# PT08tqfp.net
KiCad netlist of a schematic drawn in EAGLE
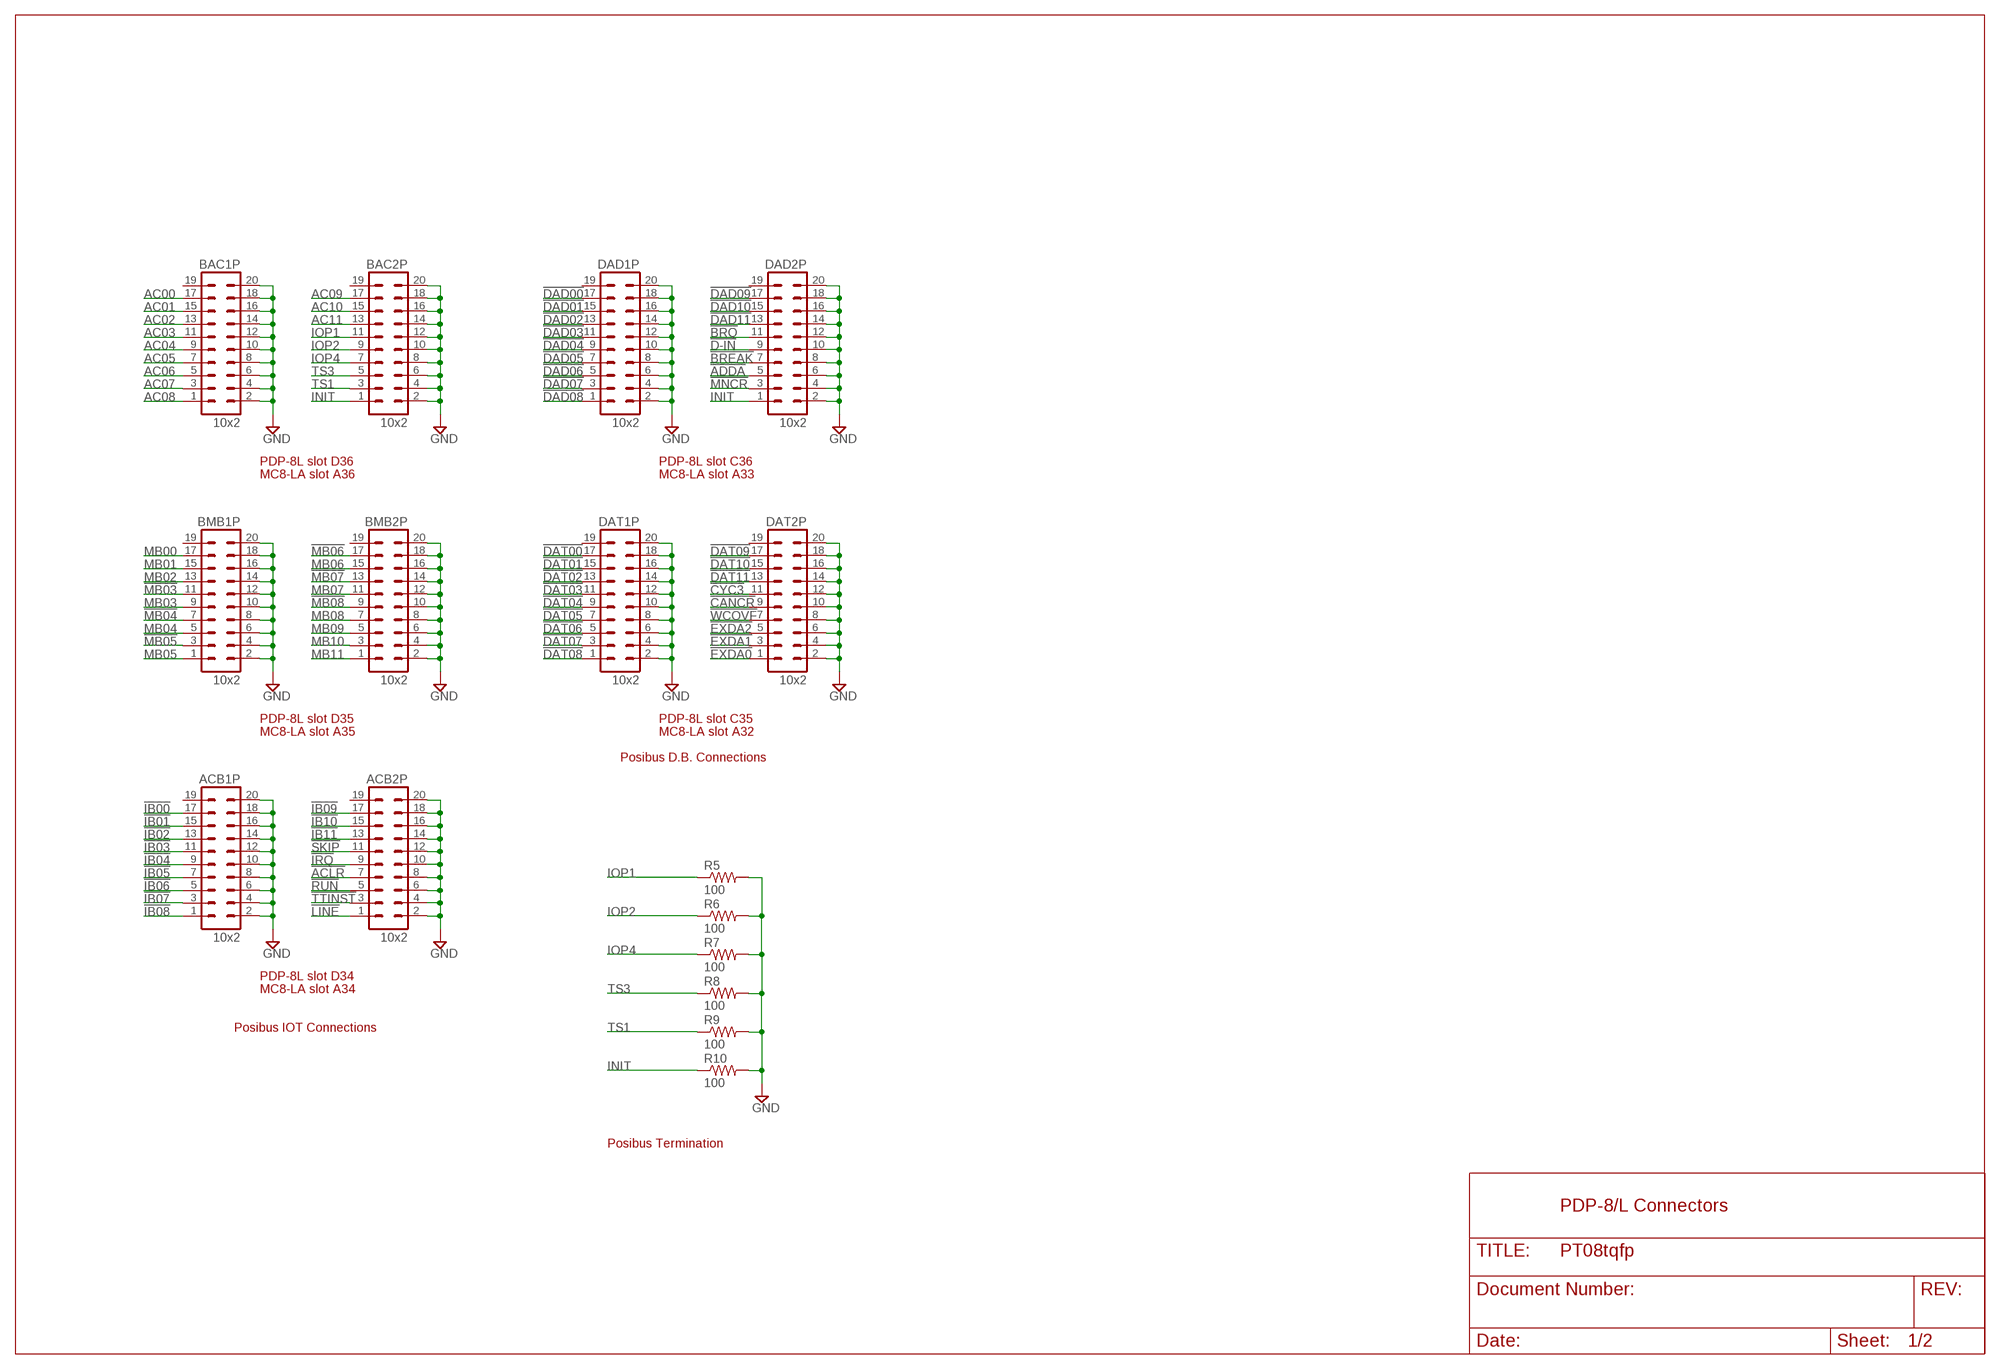
[diagram p0: schematic, sheet 1]
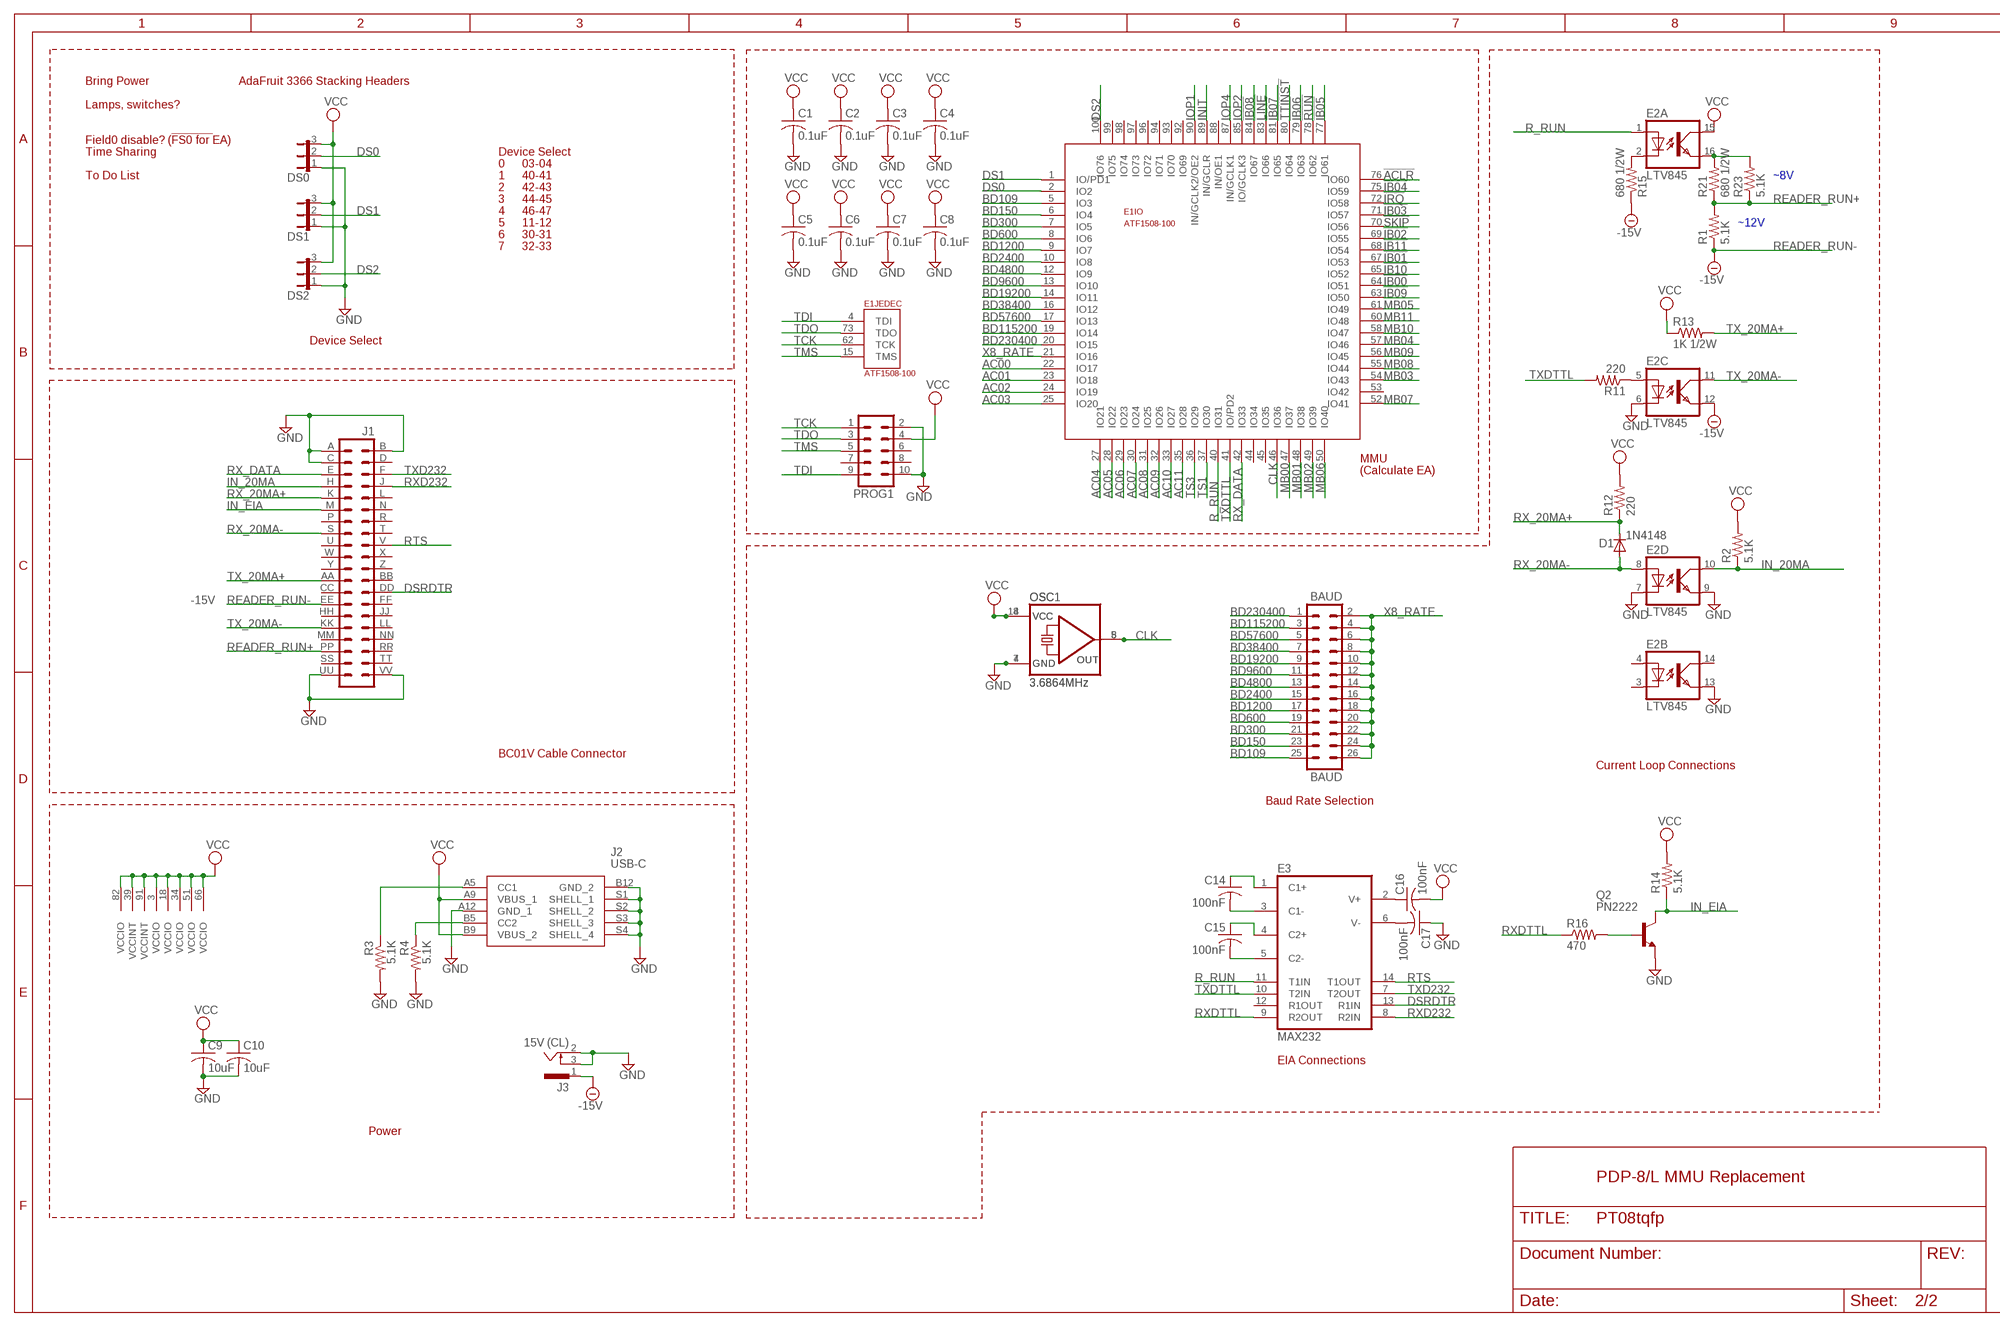
[diagram p1: schematic, sheet 2, part 1 of 2]
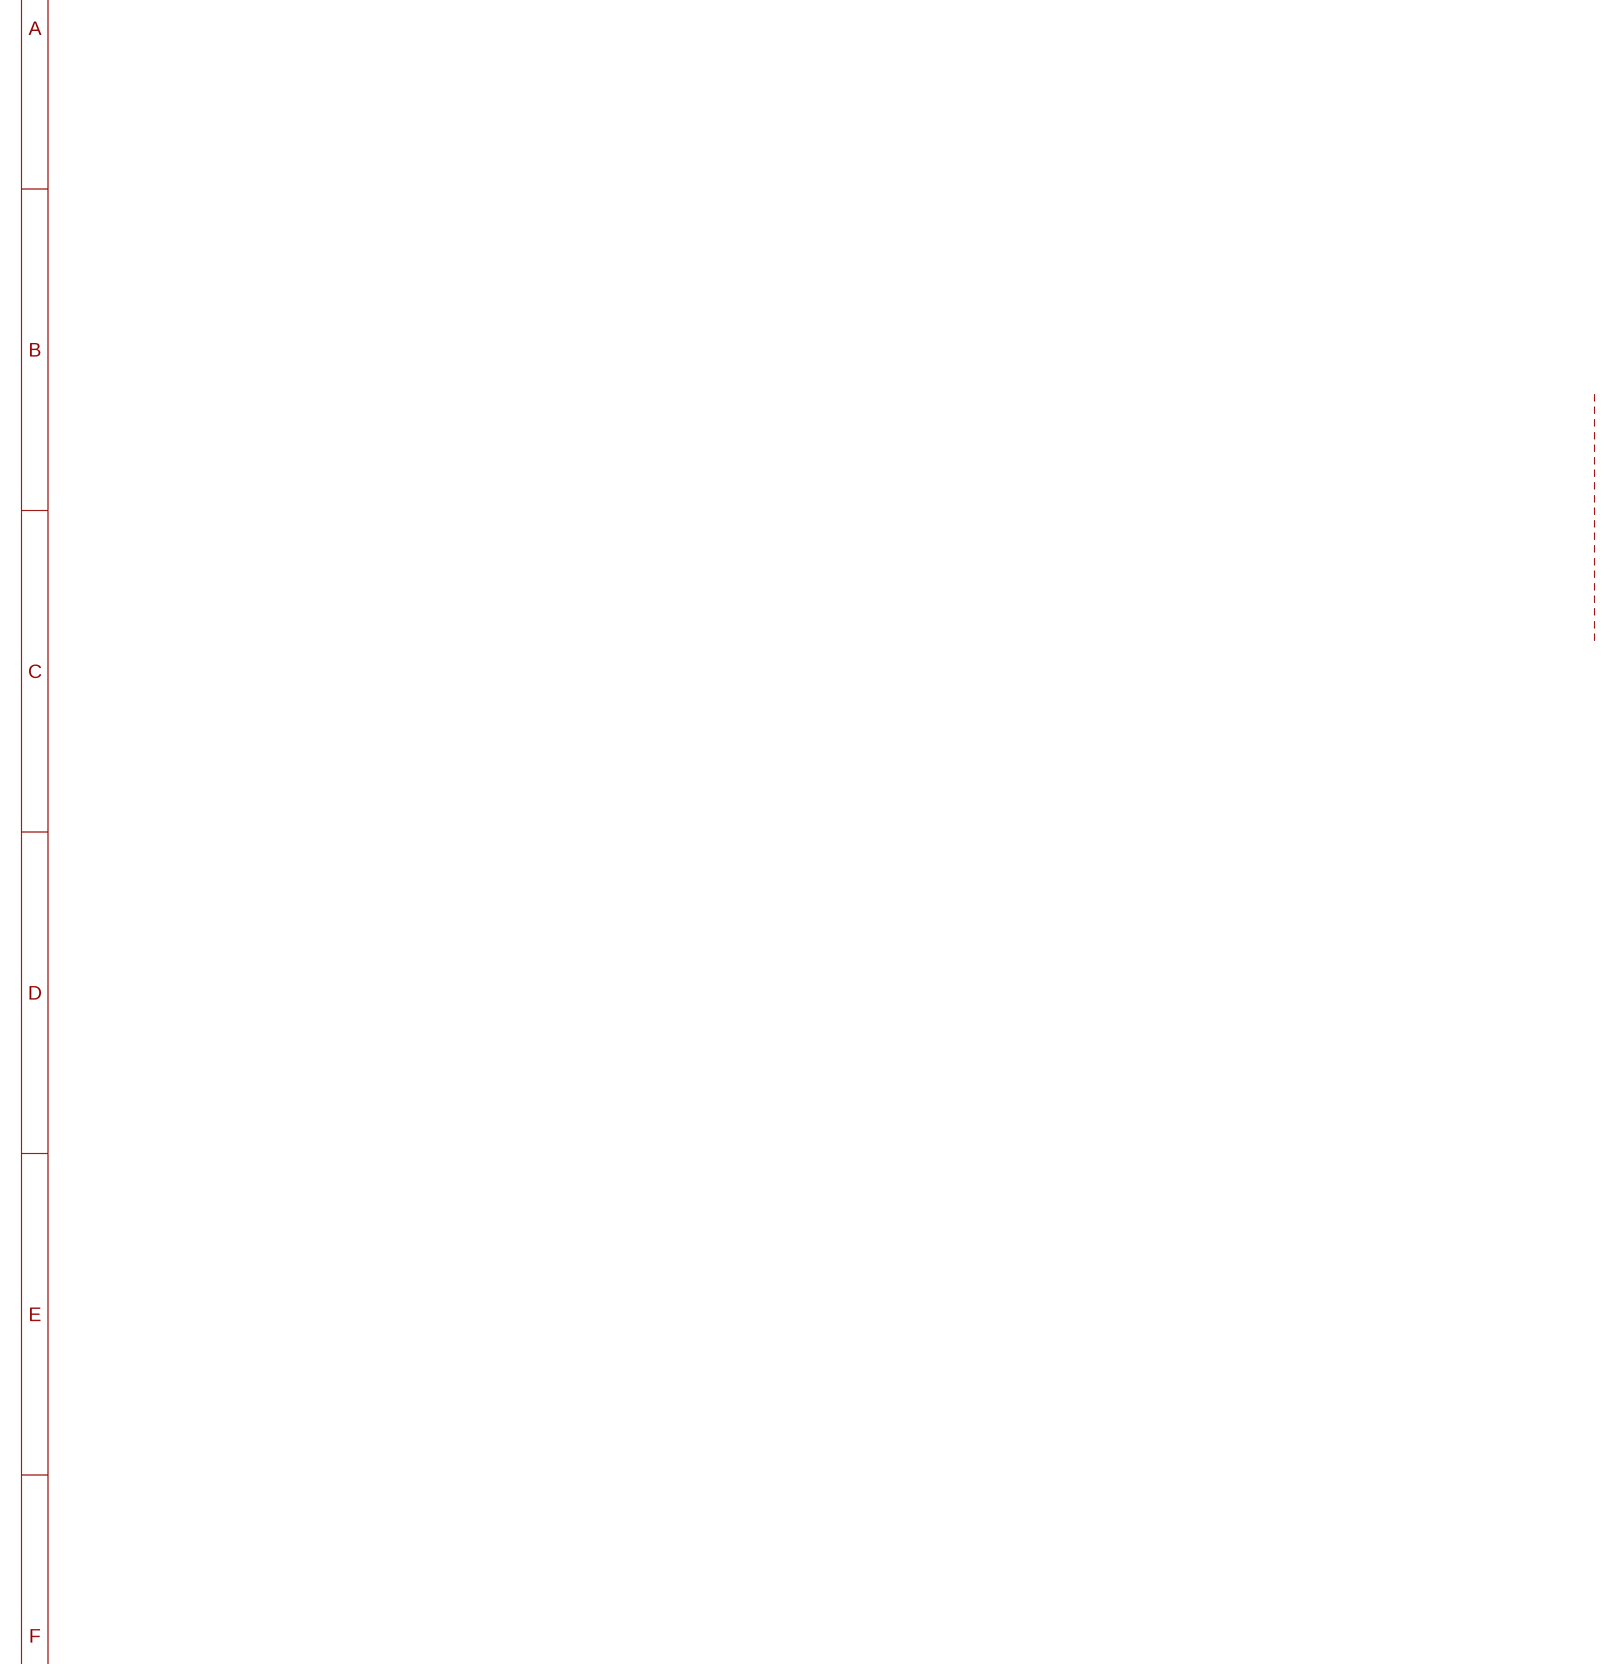
[diagram p2: schematic, sheet 2, part 2 of 2]

(export (version "E")
  (design (tool "Eeschema 10.0.6"))
  (components
    (comp (ref "ACB1P")
      (value "10x2")
      (footprint "eagle-import:MA10-2")
      (libsource (lib "eagle-import") (part "MA10-2"))
    )
    (comp (ref "ACB2P")
      (value "10x2")
      (footprint "eagle-import:MA10-2")
      (libsource (lib "eagle-import") (part "MA10-2"))
    )
    (comp (ref "BAC1P")
      (value "10x2")
      (footprint "eagle-import:MA10-2")
      (libsource (lib "eagle-import") (part "MA10-2"))
    )
    (comp (ref "BAC2P")
      (value "10x2")
      (footprint "eagle-import:MA10-2")
      (libsource (lib "eagle-import") (part "MA10-2"))
    )
    (comp (ref "BMB1P")
      (value "10x2")
      (footprint "eagle-import:MA10-2")
      (libsource (lib "eagle-import") (part "MA10-2"))
    )
    (comp (ref "BMB2P")
      (value "10x2")
      (footprint "eagle-import:MA10-2")
      (libsource (lib "eagle-import") (part "MA10-2"))
    )
    (comp (ref "DAD1P")
      (value "10x2")
      (footprint "eagle-import:MA10-2")
      (libsource (lib "eagle-import") (part "MA10-2"))
    )
    (comp (ref "DAD2P")
      (value "10x2")
      (footprint "eagle-import:MA10-2")
      (libsource (lib "eagle-import") (part "MA10-2"))
    )
    (comp (ref "DAT1P")
      (value "10x2")
      (footprint "eagle-import:MA10-2")
      (libsource (lib "eagle-import") (part "MA10-2"))
    )
    (comp (ref "DAT2P")
      (value "10x2")
      (footprint "eagle-import:MA10-2")
      (libsource (lib "eagle-import") (part "MA10-2"))
    )
    (comp (ref "R5")
      (value "100")
      (footprint "eagle-import:R1206")
      (libsource (lib "eagle-import") (part "R-US_R1206"))
    )
    (comp (ref "R6")
      (value "100")
      (footprint "eagle-import:R1206")
      (libsource (lib "eagle-import") (part "R-US_R1206"))
    )
    (comp (ref "R7")
      (value "100")
      (footprint "eagle-import:R1206")
      (libsource (lib "eagle-import") (part "R-US_R1206"))
    )
    (comp (ref "R8")
      (value "100")
      (footprint "eagle-import:R1206")
      (libsource (lib "eagle-import") (part "R-US_R1206"))
    )
    (comp (ref "R9")
      (value "100")
      (footprint "eagle-import:R1206")
      (libsource (lib "eagle-import") (part "R-US_R1206"))
    )
    (comp (ref "R10")
      (value "100")
      (footprint "eagle-import:R1206")
      (libsource (lib "eagle-import") (part "R-US_R1206"))
    )
    (comp (ref "BAUD")
      (value "BAUD")
      (footprint "eagle-import:MA13-2")
      (libsource (lib "eagle-import") (part "MA13-2"))
    )
    (comp (ref "C1")
      (value "0.1uF")
      (footprint "eagle-import:C0805")
      (libsource (lib "eagle-import") (part "C-USC0805"))
    )
    (comp (ref "C2")
      (value "0.1uF")
      (footprint "eagle-import:C0805")
      (libsource (lib "eagle-import") (part "C-USC0805"))
    )
    (comp (ref "C3")
      (value "0.1uF")
      (footprint "eagle-import:C0805")
      (libsource (lib "eagle-import") (part "C-USC0805"))
    )
    (comp (ref "C4")
      (value "0.1uF")
      (footprint "eagle-import:C0805")
      (libsource (lib "eagle-import") (part "C-USC0805"))
    )
    (comp (ref "C5")
      (value "0.1uF")
      (footprint "eagle-import:C0805")
      (libsource (lib "eagle-import") (part "C-USC0805"))
    )
    (comp (ref "C6")
      (value "0.1uF")
      (footprint "eagle-import:C0805")
      (libsource (lib "eagle-import") (part "C-USC0805"))
    )
    (comp (ref "C7")
      (value "0.1uF")
      (footprint "eagle-import:C0805")
      (libsource (lib "eagle-import") (part "C-USC0805"))
    )
    (comp (ref "C8")
      (value "0.1uF")
      (footprint "eagle-import:C0805")
      (libsource (lib "eagle-import") (part "C-USC0805"))
    )
    (comp (ref "C9")
      (value "10uF")
      (footprint "eagle-import:C0805")
      (libsource (lib "eagle-import") (part "C-USC0805"))
    )
    (comp (ref "C10")
      (value "10uF")
      (footprint "eagle-import:C0805")
      (libsource (lib "eagle-import") (part "C-USC0805"))
    )
    (comp (ref "C14")
      (value "100nF")
      (footprint "eagle-import:C0805")
      (libsource (lib "eagle-import") (part "C-USC0805"))
    )
    (comp (ref "C15")
      (value "100nF")
      (footprint "eagle-import:C0805")
      (libsource (lib "eagle-import") (part "C-USC0805"))
    )
    (comp (ref "C16")
      (value "100nF")
      (footprint "eagle-import:C0805")
      (libsource (lib "eagle-import") (part "C-USC0805"))
    )
    (comp (ref "C17")
      (value "100nF")
      (footprint "eagle-import:C0805")
      (libsource (lib "eagle-import") (part "C-USC0805"))
    )
    (comp (ref "D1")
      (value "1N4148")
      (footprint "eagle-import:SOD323-W")
      (libsource (lib "eagle-import") (part "DIODE-SOD323-W"))
    )
    (comp (ref "DS0")
      (value "JP2E")
      (footprint "eagle-import:JP2")
      (libsource (lib "eagle-import") (part "JP2E"))
    )
    (comp (ref "DS1")
      (value "JP2E")
      (footprint "eagle-import:JP2")
      (libsource (lib "eagle-import") (part "JP2E"))
    )
    (comp (ref "DS2")
      (value "JP2E")
      (footprint "eagle-import:JP2")
      (libsource (lib "eagle-import") (part "JP2E"))
    )
    (comp (ref "E1")
      (value "ATF1508-100")
      (footprint "eagle-import:TQFP-100")
      (libsource (lib "eagle-import") (part "ATF150X100TQFP"))
    )
    (comp (ref "E2")
      (value "LTV845")
      (footprint "eagle-import:DIL16")
      (fields (field (name "MF") "VISHAY/TELEFUNKEN") (field (name "MPN") "ILQ1"))
      (libsource (lib "eagle-import") (part "ILQ1"))
    )
    (comp (ref "E3")
      (value "MAX232")
      (footprint "eagle-import:DIL16")
      (fields (field (name "MF") "MAXIM") (field (name "MPN") "MAX232ACPE+"))
      (libsource (lib "eagle-import") (part "MAX232"))
    )
    (comp (ref "J1")
      (value "DEC40PINH")
      (footprint "eagle-import:DEC40PINH")
      (libsource (lib "eagle-import") (part "DEC40PINH"))
    )
    (comp (ref "J2")
      (value "USB-C")
      (footprint "eagle-import:USB497000A")
      (fields (field (name "MANUFACTURER_PART_NUMBER") "USB4970-00-A"))
      (libsource (lib "eagle-import") (part "USB4970-00-A"))
    )
    (comp (ref "J3")
      (value "15V (CL)")
      (footprint "eagle-import:SCD-014-A")
      (libsource (lib "eagle-import") (part "SCD-014A"))
    )
    (comp (ref "OSC")
      (value "3.6864MHz")
      (footprint "eagle-import:DIL08S")
      (libsource (lib "eagle-import") (part "QG5460"))
    )
    (comp (ref "OSC1")
      (value "3.6864MHz")
      (footprint "eagle-import:DIL14S")
      (libsource (lib "eagle-import") (part "QG5860"))
    )
    (comp (ref "PROG1")
      (value "ML10")
      (footprint "eagle-import:ML10")
      (libsource (lib "eagle-import") (part "ML10"))
    )
    (comp (ref "Q2")
      (value "PN2222")
      (footprint "eagle-import:SOT23-EBC")
      (libsource (lib "eagle-import") (part "-NPN-SOT23-EBC"))
    )
    (comp (ref "R1")
      (value "5.1K")
      (footprint "eagle-import:R0805")
      (libsource (lib "eagle-import") (part "R-US_R0805"))
    )
    (comp (ref "R2")
      (value "5.1K")
      (footprint "eagle-import:R0805")
      (libsource (lib "eagle-import") (part "R-US_R0805"))
    )
    (comp (ref "R3")
      (value "5.1K")
      (footprint "eagle-import:R0805")
      (libsource (lib "eagle-import") (part "R-US_R0805"))
    )
    (comp (ref "R4")
      (value "5.1K")
      (footprint "eagle-import:R0805")
      (libsource (lib "eagle-import") (part "R-US_R0805"))
    )
    (comp (ref "R11")
      (value "220")
      (footprint "eagle-import:R0805")
      (libsource (lib "eagle-import") (part "R-US_R0805"))
    )
    (comp (ref "R12")
      (value "220")
      (footprint "eagle-import:R0805")
      (libsource (lib "eagle-import") (part "R-US_R0805"))
    )
    (comp (ref "R13")
      (value "1K 1/2W")
      (footprint "eagle-import:0207_10")
      (libsource (lib "eagle-import") (part "R-US_0207/10"))
    )
    (comp (ref "R14")
      (value "5.1K")
      (footprint "eagle-import:R0805")
      (libsource (lib "eagle-import") (part "R-US_R0805"))
    )
    (comp (ref "R15")
      (value "680 1/2W")
      (footprint "eagle-import:0207_10")
      (libsource (lib "eagle-import") (part "R-US_0207/10"))
    )
    (comp (ref "R16")
      (value "470")
      (footprint "eagle-import:R0805")
      (libsource (lib "eagle-import") (part "R-US_R0805"))
    )
    (comp (ref "R21")
      (value "680 1/2W")
      (footprint "eagle-import:0207_10")
      (libsource (lib "eagle-import") (part "R-US_0207/10"))
    )
    (comp (ref "R23")
      (value "5.1K")
      (footprint "eagle-import:R0805")
      (libsource (lib "eagle-import") (part "R-US_R0805"))
    )
  )
  (nets
    (net (code "1") (name "-15V") (class "Default")
      (node (ref "E2") (pin "12") (pinfunction "EMIT_12") (pintype "passive"))
      (node (ref "J1") (pin "EE") (pinfunction "27_EE") (pintype "bidirectional"))
      (node (ref "J3") (pin "1") (pinfunction "1_1") (pintype "passive"))
      (node (ref "R1") (pin "1") (pinfunction "1_1") (pintype "passive"))
      (node (ref "R15") (pin "1") (pinfunction "1_1") (pintype "passive"))
    )
    (net (code "2") (name "AC00") (class "Default")
      (node (ref "BAC1P") (pin "17") (pinfunction "17_17") (pintype "passive"))
      (node (ref "E1") (pin "22") (pinfunction "IO17_22") (pintype "bidirectional"))
    )
    (net (code "3") (name "AC01") (class "Default")
      (node (ref "BAC1P") (pin "15") (pinfunction "15_15") (pintype "passive"))
      (node (ref "E1") (pin "23") (pinfunction "IO18_23") (pintype "bidirectional"))
    )
    (net (code "4") (name "AC02") (class "Default")
      (node (ref "BAC1P") (pin "13") (pinfunction "13_13") (pintype "passive"))
      (node (ref "E1") (pin "24") (pinfunction "IO19_24") (pintype "bidirectional"))
    )
    (net (code "5") (name "AC03") (class "Default")
      (node (ref "BAC1P") (pin "11") (pinfunction "11_11") (pintype "passive"))
      (node (ref "E1") (pin "25") (pinfunction "IO20_25") (pintype "bidirectional"))
    )
    (net (code "6") (name "AC04") (class "Default")
      (node (ref "BAC1P") (pin "9") (pinfunction "9_9") (pintype "passive"))
      (node (ref "E1") (pin "27") (pinfunction "IO21_27") (pintype "bidirectional"))
    )
    (net (code "7") (name "AC05") (class "Default")
      (node (ref "BAC1P") (pin "7") (pinfunction "7_7") (pintype "passive"))
      (node (ref "E1") (pin "28") (pinfunction "IO22_28") (pintype "bidirectional"))
    )
    (net (code "8") (name "AC06") (class "Default")
      (node (ref "BAC1P") (pin "5") (pinfunction "5_5") (pintype "passive"))
      (node (ref "E1") (pin "29") (pinfunction "IO23_29") (pintype "bidirectional"))
    )
    (net (code "9") (name "AC07") (class "Default")
      (node (ref "BAC1P") (pin "3") (pinfunction "3_3") (pintype "passive"))
      (node (ref "E1") (pin "30") (pinfunction "IO24_30") (pintype "bidirectional"))
    )
    (net (code "10") (name "AC08") (class "Default")
      (node (ref "BAC1P") (pin "1") (pinfunction "1_1") (pintype "passive"))
      (node (ref "E1") (pin "31") (pinfunction "IO25_31") (pintype "bidirectional"))
    )
    (net (code "11") (name "AC09") (class "Default")
      (node (ref "BAC2P") (pin "17") (pinfunction "17_17") (pintype "passive"))
      (node (ref "E1") (pin "32") (pinfunction "IO26_32") (pintype "bidirectional"))
    )
    (net (code "12") (name "AC10") (class "Default")
      (node (ref "BAC2P") (pin "15") (pinfunction "15_15") (pintype "passive"))
      (node (ref "E1") (pin "33") (pinfunction "IO27_33") (pintype "bidirectional"))
    )
    (net (code "13") (name "AC11") (class "Default")
      (node (ref "BAC2P") (pin "13") (pinfunction "13_13") (pintype "passive"))
      (node (ref "E1") (pin "35") (pinfunction "IO28_35") (pintype "bidirectional"))
    )
    (net (code "14") (name "BD109") (class "Default")
      (node (ref "BAUD") (pin "25") (pinfunction "25_25") (pintype "passive"))
      (node (ref "E1") (pin "5") (pinfunction "IO3_5") (pintype "bidirectional"))
    )
    (net (code "15") (name "BD150") (class "Default")
      (node (ref "BAUD") (pin "23") (pinfunction "23_23") (pintype "passive"))
      (node (ref "E1") (pin "6") (pinfunction "IO4_6") (pintype "bidirectional"))
    )
    (net (code "16") (name "BD300") (class "Default")
      (node (ref "BAUD") (pin "21") (pinfunction "21_21") (pintype "passive"))
      (node (ref "E1") (pin "7") (pinfunction "IO5_7") (pintype "bidirectional"))
    )
    (net (code "17") (name "BD600") (class "Default")
      (node (ref "BAUD") (pin "19") (pinfunction "19_19") (pintype "passive"))
      (node (ref "E1") (pin "8") (pinfunction "IO6_8") (pintype "bidirectional"))
    )
    (net (code "18") (name "BD1200") (class "Default")
      (node (ref "BAUD") (pin "17") (pinfunction "17_17") (pintype "passive"))
      (node (ref "E1") (pin "9") (pinfunction "IO7_9") (pintype "bidirectional"))
    )
    (net (code "19") (name "BD2400") (class "Default")
      (node (ref "BAUD") (pin "15") (pinfunction "15_15") (pintype "passive"))
      (node (ref "E1") (pin "10") (pinfunction "IO8_10") (pintype "bidirectional"))
    )
    (net (code "20") (name "BD4800") (class "Default")
      (node (ref "BAUD") (pin "13") (pinfunction "13_13") (pintype "passive"))
      (node (ref "E1") (pin "12") (pinfunction "IO9_12") (pintype "bidirectional"))
    )
    (net (code "21") (name "BD9600") (class "Default")
      (node (ref "BAUD") (pin "11") (pinfunction "11_11") (pintype "passive"))
      (node (ref "E1") (pin "13") (pinfunction "IO10_13") (pintype "bidirectional"))
    )
    (net (code "22") (name "BD19200") (class "Default")
      (node (ref "BAUD") (pin "9") (pinfunction "9_9") (pintype "passive"))
      (node (ref "E1") (pin "14") (pinfunction "IO11_14") (pintype "bidirectional"))
    )
    (net (code "23") (name "BD38400") (class "Default")
      (node (ref "BAUD") (pin "7") (pinfunction "7_7") (pintype "passive"))
      (node (ref "E1") (pin "16") (pinfunction "IO12_16") (pintype "bidirectional"))
    )
    (net (code "24") (name "BD57600") (class "Default")
      (node (ref "BAUD") (pin "5") (pinfunction "5_5") (pintype "passive"))
      (node (ref "E1") (pin "17") (pinfunction "IO13_17") (pintype "bidirectional"))
    )
    (net (code "25") (name "BD115200") (class "Default")
      (node (ref "BAUD") (pin "3") (pinfunction "3_3") (pintype "passive"))
      (node (ref "E1") (pin "19") (pinfunction "IO14_19") (pintype "bidirectional"))
    )
    (net (code "26") (name "BD230400") (class "Default")
      (node (ref "BAUD") (pin "1") (pinfunction "1_1") (pintype "passive"))
      (node (ref "E1") (pin "20") (pinfunction "IO15_20") (pintype "bidirectional"))
    )
    (net (code "27") (name "CLK") (class "Default")
      (node (ref "E1") (pin "46") (pinfunction "IO36_46") (pintype "bidirectional"))
      (node (ref "OSC") (pin "5") (pinfunction "OUT_5") (pintype "output"))
      (node (ref "OSC1") (pin "8") (pinfunction "OUT_8") (pintype "output"))
    )
    (net (code "28") (name "DS0") (class "Default")
      (node (ref "DS0") (pin "2") (pinfunction "2_2") (pintype "passive"))
      (node (ref "E1") (pin "2") (pinfunction "IO2_2") (pintype "bidirectional"))
    )
    (net (code "29") (name "DS1") (class "Default")
      (node (ref "DS1") (pin "2") (pinfunction "2_2") (pintype "passive"))
      (node (ref "E1") (pin "1") (pinfunction "IO/PD1_1") (pintype "bidirectional"))
    )
    (net (code "30") (name "DS2") (class "Default")
      (node (ref "DS2") (pin "2") (pinfunction "2_2") (pintype "passive"))
      (node (ref "E1") (pin "100") (pinfunction "IO76_100") (pintype "bidirectional"))
    )
    (net (code "31") (name "DSRDTR") (class "Default")
      (node (ref "E3") (pin "13") (pinfunction "R1IN_13") (pintype "input"))
      (node (ref "J1") (pin "DD") (pinfunction "26_DD") (pintype "bidirectional"))
    )
    (net (code "32") (name "GND") (class "Default")
      (node (ref "ACB1P") (pin "10") (pinfunction "10_10") (pintype "passive"))
      (node (ref "ACB1P") (pin "12") (pinfunction "12_12") (pintype "passive"))
      (node (ref "ACB1P") (pin "14") (pinfunction "14_14") (pintype "passive"))
      (node (ref "ACB1P") (pin "16") (pinfunction "16_16") (pintype "passive"))
      (node (ref "ACB1P") (pin "18") (pinfunction "18_18") (pintype "passive"))
      (node (ref "ACB1P") (pin "2") (pinfunction "2_2") (pintype "passive"))
      (node (ref "ACB1P") (pin "20") (pinfunction "20_20") (pintype "passive"))
      (node (ref "ACB1P") (pin "4") (pinfunction "4_4") (pintype "passive"))
      (node (ref "ACB1P") (pin "6") (pinfunction "6_6") (pintype "passive"))
      (node (ref "ACB1P") (pin "8") (pinfunction "8_8") (pintype "passive"))
      (node (ref "ACB2P") (pin "10") (pinfunction "10_10") (pintype "passive"))
      (node (ref "ACB2P") (pin "12") (pinfunction "12_12") (pintype "passive"))
      (node (ref "ACB2P") (pin "14") (pinfunction "14_14") (pintype "passive"))
      (node (ref "ACB2P") (pin "16") (pinfunction "16_16") (pintype "passive"))
      (node (ref "ACB2P") (pin "18") (pinfunction "18_18") (pintype "passive"))
      (node (ref "ACB2P") (pin "2") (pinfunction "2_2") (pintype "passive"))
      (node (ref "ACB2P") (pin "20") (pinfunction "20_20") (pintype "passive"))
      (node (ref "ACB2P") (pin "4") (pinfunction "4_4") (pintype "passive"))
      (node (ref "ACB2P") (pin "6") (pinfunction "6_6") (pintype "passive"))
      (node (ref "ACB2P") (pin "8") (pinfunction "8_8") (pintype "passive"))
      (node (ref "BAC1P") (pin "10") (pinfunction "10_10") (pintype "passive"))
      (node (ref "BAC1P") (pin "12") (pinfunction "12_12") (pintype "passive"))
      (node (ref "BAC1P") (pin "14") (pinfunction "14_14") (pintype "passive"))
      (node (ref "BAC1P") (pin "16") (pinfunction "16_16") (pintype "passive"))
      (node (ref "BAC1P") (pin "18") (pinfunction "18_18") (pintype "passive"))
      (node (ref "BAC1P") (pin "2") (pinfunction "2_2") (pintype "passive"))
      (node (ref "BAC1P") (pin "20") (pinfunction "20_20") (pintype "passive"))
      (node (ref "BAC1P") (pin "4") (pinfunction "4_4") (pintype "passive"))
      (node (ref "BAC1P") (pin "6") (pinfunction "6_6") (pintype "passive"))
      (node (ref "BAC1P") (pin "8") (pinfunction "8_8") (pintype "passive"))
      (node (ref "BAC2P") (pin "10") (pinfunction "10_10") (pintype "passive"))
      (node (ref "BAC2P") (pin "12") (pinfunction "12_12") (pintype "passive"))
      (node (ref "BAC2P") (pin "14") (pinfunction "14_14") (pintype "passive"))
      (node (ref "BAC2P") (pin "16") (pinfunction "16_16") (pintype "passive"))
      (node (ref "BAC2P") (pin "18") (pinfunction "18_18") (pintype "passive"))
      (node (ref "BAC2P") (pin "2") (pinfunction "2_2") (pintype "passive"))
      (node (ref "BAC2P") (pin "20") (pinfunction "20_20") (pintype "passive"))
      (node (ref "BAC2P") (pin "4") (pinfunction "4_4") (pintype "passive"))
      (node (ref "BAC2P") (pin "6") (pinfunction "6_6") (pintype "passive"))
      (node (ref "BAC2P") (pin "8") (pinfunction "8_8") (pintype "passive"))
      (node (ref "BMB1P") (pin "10") (pinfunction "10_10") (pintype "passive"))
      (node (ref "BMB1P") (pin "12") (pinfunction "12_12") (pintype "passive"))
      (node (ref "BMB1P") (pin "14") (pinfunction "14_14") (pintype "passive"))
      (node (ref "BMB1P") (pin "16") (pinfunction "16_16") (pintype "passive"))
      (node (ref "BMB1P") (pin "18") (pinfunction "18_18") (pintype "passive"))
      (node (ref "BMB1P") (pin "2") (pinfunction "2_2") (pintype "passive"))
      (node (ref "BMB1P") (pin "20") (pinfunction "20_20") (pintype "passive"))
      (node (ref "BMB1P") (pin "4") (pinfunction "4_4") (pintype "passive"))
      (node (ref "BMB1P") (pin "6") (pinfunction "6_6") (pintype "passive"))
      (node (ref "BMB1P") (pin "8") (pinfunction "8_8") (pintype "passive"))
      (node (ref "BMB2P") (pin "10") (pinfunction "10_10") (pintype "passive"))
      (node (ref "BMB2P") (pin "12") (pinfunction "12_12") (pintype "passive"))
      (node (ref "BMB2P") (pin "14") (pinfunction "14_14") (pintype "passive"))
      (node (ref "BMB2P") (pin "16") (pinfunction "16_16") (pintype "passive"))
      (node (ref "BMB2P") (pin "18") (pinfunction "18_18") (pintype "passive"))
      (node (ref "BMB2P") (pin "2") (pinfunction "2_2") (pintype "passive"))
      (node (ref "BMB2P") (pin "20") (pinfunction "20_20") (pintype "passive"))
      (node (ref "BMB2P") (pin "4") (pinfunction "4_4") (pintype "passive"))
      (node (ref "BMB2P") (pin "6") (pinfunction "6_6") (pintype "passive"))
      (node (ref "BMB2P") (pin "8") (pinfunction "8_8") (pintype "passive"))
      (node (ref "C1") (pin "2") (pinfunction "2_2") (pintype "passive"))
      (node (ref "C10") (pin "2") (pinfunction "2_2") (pintype "passive"))
      (node (ref "C17") (pin "1") (pinfunction "1_1") (pintype "passive"))
      (node (ref "C2") (pin "2") (pinfunction "2_2") (pintype "passive"))
      (node (ref "C3") (pin "2") (pinfunction "2_2") (pintype "passive"))
      (node (ref "C4") (pin "2") (pinfunction "2_2") (pintype "passive"))
      (node (ref "C5") (pin "2") (pinfunction "2_2") (pintype "passive"))
      (node (ref "C6") (pin "2") (pinfunction "2_2") (pintype "passive"))
      (node (ref "C7") (pin "2") (pinfunction "2_2") (pintype "passive"))
      (node (ref "C8") (pin "2") (pinfunction "2_2") (pintype "passive"))
      (node (ref "C9") (pin "2") (pinfunction "2_2") (pintype "passive"))
      (node (ref "DAD1P") (pin "10") (pinfunction "10_10") (pintype "passive"))
      (node (ref "DAD1P") (pin "12") (pinfunction "12_12") (pintype "passive"))
      (node (ref "DAD1P") (pin "14") (pinfunction "14_14") (pintype "passive"))
      (node (ref "DAD1P") (pin "16") (pinfunction "16_16") (pintype "passive"))
      (node (ref "DAD1P") (pin "18") (pinfunction "18_18") (pintype "passive"))
      (node (ref "DAD1P") (pin "2") (pinfunction "2_2") (pintype "passive"))
      (node (ref "DAD1P") (pin "20") (pinfunction "20_20") (pintype "passive"))
      (node (ref "DAD1P") (pin "4") (pinfunction "4_4") (pintype "passive"))
      (node (ref "DAD1P") (pin "6") (pinfunction "6_6") (pintype "passive"))
      (node (ref "DAD1P") (pin "8") (pinfunction "8_8") (pintype "passive"))
      (node (ref "DAD2P") (pin "10") (pinfunction "10_10") (pintype "passive"))
      (node (ref "DAD2P") (pin "12") (pinfunction "12_12") (pintype "passive"))
      (node (ref "DAD2P") (pin "14") (pinfunction "14_14") (pintype "passive"))
      (node (ref "DAD2P") (pin "16") (pinfunction "16_16") (pintype "passive"))
      (node (ref "DAD2P") (pin "18") (pinfunction "18_18") (pintype "passive"))
      (node (ref "DAD2P") (pin "2") (pinfunction "2_2") (pintype "passive"))
      (node (ref "DAD2P") (pin "20") (pinfunction "20_20") (pintype "passive"))
      (node (ref "DAD2P") (pin "4") (pinfunction "4_4") (pintype "passive"))
      (node (ref "DAD2P") (pin "6") (pinfunction "6_6") (pintype "passive"))
      (node (ref "DAD2P") (pin "8") (pinfunction "8_8") (pintype "passive"))
      (node (ref "DAT1P") (pin "10") (pinfunction "10_10") (pintype "passive"))
      (node (ref "DAT1P") (pin "12") (pinfunction "12_12") (pintype "passive"))
      (node (ref "DAT1P") (pin "14") (pinfunction "14_14") (pintype "passive"))
      (node (ref "DAT1P") (pin "16") (pinfunction "16_16") (pintype "passive"))
      (node (ref "DAT1P") (pin "18") (pinfunction "18_18") (pintype "passive"))
      (node (ref "DAT1P") (pin "2") (pinfunction "2_2") (pintype "passive"))
      (node (ref "DAT1P") (pin "20") (pinfunction "20_20") (pintype "passive"))
      (node (ref "DAT1P") (pin "4") (pinfunction "4_4") (pintype "passive"))
      (node (ref "DAT1P") (pin "6") (pinfunction "6_6") (pintype "passive"))
      (node (ref "DAT1P") (pin "8") (pinfunction "8_8") (pintype "passive"))
      (node (ref "DAT2P") (pin "10") (pinfunction "10_10") (pintype "passive"))
      (node (ref "DAT2P") (pin "12") (pinfunction "12_12") (pintype "passive"))
      (node (ref "DAT2P") (pin "14") (pinfunction "14_14") (pintype "passive"))
      (node (ref "DAT2P") (pin "16") (pinfunction "16_16") (pintype "passive"))
      (node (ref "DAT2P") (pin "18") (pinfunction "18_18") (pintype "passive"))
      (node (ref "DAT2P") (pin "2") (pinfunction "2_2") (pintype "passive"))
      (node (ref "DAT2P") (pin "20") (pinfunction "20_20") (pintype "passive"))
      (node (ref "DAT2P") (pin "4") (pinfunction "4_4") (pintype "passive"))
      (node (ref "DAT2P") (pin "6") (pinfunction "6_6") (pintype "passive"))
      (node (ref "DAT2P") (pin "8") (pinfunction "8_8") (pintype "passive"))
      (node (ref "DS0") (pin "1") (pinfunction "1_1") (pintype "passive"))
      (node (ref "DS1") (pin "1") (pinfunction "1_1") (pintype "passive"))
      (node (ref "DS2") (pin "1") (pinfunction "1_1") (pintype "passive"))
      (node (ref "E2") (pin "13") (pinfunction "EMIT_13") (pintype "passive"))
      (node (ref "E2") (pin "6") (pinfunction "C_6") (pintype "passive"))
      (node (ref "E2") (pin "7") (pinfunction "C_7") (pintype "passive"))
      (node (ref "E2") (pin "9") (pinfunction "EMIT_9") (pintype "passive"))
      (node (ref "J1") (pin "A") (pinfunction "1_A") (pintype "bidirectional"))
      (node (ref "J1") (pin "B") (pinfunction "2_B") (pintype "bidirectional"))
      (node (ref "J1") (pin "C") (pinfunction "3_C") (pintype "bidirectional"))
      (node (ref "J1") (pin "UU") (pinfunction "39_UU") (pintype "bidirectional"))
      (node (ref "J1") (pin "VV") (pinfunction "40_VV") (pintype "bidirectional"))
      (node (ref "J2") (pin "A12") (pinfunction "GND_1_A12") (pintype "bidirectional"))
      (node (ref "J2") (pin "B12") (pinfunction "GND_2_B12") (pintype "bidirectional"))
      (node (ref "J2") (pin "S1") (pinfunction "SHELL_1_S1") (pintype "bidirectional"))
      (node (ref "J2") (pin "S2") (pinfunction "SHELL_2_S2") (pintype "bidirectional"))
      (node (ref "J2") (pin "S3") (pinfunction "SHELL_3_S3") (pintype "bidirectional"))
      (node (ref "J2") (pin "S4") (pinfunction "SHELL_4_S4") (pintype "bidirectional"))
      (node (ref "J3") (pin "2") (pinfunction "2_2") (pintype "passive"))
      (node (ref "J3") (pin "3") (pinfunction "3_3") (pintype "passive"))
      (node (ref "OSC") (pin "4") (pinfunction "GND_4") (pintype "power_in"))
      (node (ref "OSC1") (pin "7") (pinfunction "GND_7") (pintype "power_in"))
      (node (ref "PROG1") (pin "10") (pinfunction "10_10") (pintype "passive"))
      (node (ref "PROG1") (pin "2") (pinfunction "2_2") (pintype "passive"))
      (node (ref "Q2") (pin "E") (pinfunction "E_E") (pintype "passive"))
      (node (ref "R10") (pin "2") (pinfunction "2_2") (pintype "passive"))
      (node (ref "R3") (pin "2") (pinfunction "2_2") (pintype "passive"))
      (node (ref "R4") (pin "2") (pinfunction "2_2") (pintype "passive"))
      (node (ref "R5") (pin "2") (pinfunction "2_2") (pintype "passive"))
      (node (ref "R6") (pin "2") (pinfunction "2_2") (pintype "passive"))
      (node (ref "R7") (pin "2") (pinfunction "2_2") (pintype "passive"))
      (node (ref "R8") (pin "2") (pinfunction "2_2") (pintype "passive"))
      (node (ref "R9") (pin "2") (pinfunction "2_2") (pintype "passive"))
    )
    (net (code "33") (name "INIT") (class "Default")
      (node (ref "BAC2P") (pin "1") (pinfunction "1_1") (pintype "passive"))
      (node (ref "DAD2P") (pin "1") (pinfunction "1_1") (pintype "passive"))
      (node (ref "E1") (pin "89") (pinfunction "IN/GCLR_89") (pintype "input"))
      (node (ref "R10") (pin "1") (pinfunction "1_1") (pintype "passive"))
    )
    (net (code "34") (name "IN_20MA") (class "Default")
      (node (ref "E2") (pin "10") (pinfunction "COL_10") (pintype "passive"))
      (node (ref "J1") (pin "H") (pinfunction "7_H") (pintype "bidirectional"))
      (node (ref "R2") (pin "1") (pinfunction "1_1") (pintype "passive"))
    )
    (net (code "35") (name "IN_EIA") (class "Default")
      (node (ref "J1") (pin "M") (pinfunction "11_M") (pintype "bidirectional"))
      (node (ref "Q2") (pin "C") (pinfunction "C_C") (pintype "passive"))
      (node (ref "R14") (pin "1") (pinfunction "1_1") (pintype "passive"))
    )
    (net (code "36") (name "IOP1") (class "Default")
      (node (ref "BAC2P") (pin "11") (pinfunction "11_11") (pintype "passive"))
      (node (ref "E1") (pin "90") (pinfunction "IN/GCLK2/OE2_90") (pintype "input"))
      (node (ref "R5") (pin "1") (pinfunction "1_1") (pintype "passive"))
    )
    (net (code "37") (name "IOP2") (class "Default")
      (node (ref "BAC2P") (pin "9") (pinfunction "9_9") (pintype "passive"))
      (node (ref "E1") (pin "85") (pinfunction "IO/GCLK3_85") (pintype "bidirectional"))
      (node (ref "R6") (pin "1") (pinfunction "1_1") (pintype "passive"))
    )
    (net (code "38") (name "IOP4") (class "Default")
      (node (ref "BAC2P") (pin "7") (pinfunction "7_7") (pintype "passive"))
      (node (ref "E1") (pin "87") (pinfunction "IN/GCLK1_87") (pintype "input"))
      (node (ref "R7") (pin "1") (pinfunction "1_1") (pintype "passive"))
    )
    (net (code "39") (name "MB00") (class "Default")
      (node (ref "BMB1P") (pin "17") (pinfunction "17_17") (pintype "passive"))
      (node (ref "E1") (pin "47") (pinfunction "IO37_47") (pintype "bidirectional"))
    )
    (net (code "40") (name "MB01") (class "Default")
      (node (ref "BMB1P") (pin "15") (pinfunction "15_15") (pintype "passive"))
      (node (ref "E1") (pin "48") (pinfunction "IO38_48") (pintype "bidirectional"))
    )
    (net (code "41") (name "MB02") (class "Default")
      (node (ref "BMB1P") (pin "13") (pinfunction "13_13") (pintype "passive"))
      (node (ref "E1") (pin "49") (pinfunction "IO39_49") (pintype "bidirectional"))
    )
    (net (code "42") (name "MB03") (class "Default")
      (node (ref "BMB1P") (pin "9") (pinfunction "9_9") (pintype "passive"))
      (node (ref "E1") (pin "54") (pinfunction "IO43_54") (pintype "bidirectional"))
    )
    (net (code "43") (name "MB04") (class "Default")
      (node (ref "BMB1P") (pin "5") (pinfunction "5_5") (pintype "passive"))
      (node (ref "E1") (pin "57") (pinfunction "IO46_57") (pintype "bidirectional"))
    )
    (net (code "44") (name "MB05") (class "Default")
      (node (ref "BMB1P") (pin "1") (pinfunction "1_1") (pintype "passive"))
      (node (ref "E1") (pin "61") (pinfunction "IO49_61") (pintype "bidirectional"))
    )
    (net (code "45") (name "MB06") (class "Default")
      (node (ref "BMB2P") (pin "15") (pinfunction "15_15") (pintype "passive"))
      (node (ref "E1") (pin "50") (pinfunction "IO40_50") (pintype "bidirectional"))
    )
    (net (code "46") (name "MB07") (class "Default")
      (node (ref "BMB2P") (pin "11") (pinfunction "11_11") (pintype "passive"))
      (node (ref "E1") (pin "52") (pinfunction "IO41_52") (pintype "bidirectional"))
    )
    (net (code "47") (name "MB08") (class "Default")
      (node (ref "BMB2P") (pin "7") (pinfunction "7_7") (pintype "passive"))
      (node (ref "E1") (pin "55") (pinfunction "IO44_55") (pintype "bidirectional"))
    )
    (net (code "48") (name "MB09") (class "Default")
      (node (ref "BMB2P") (pin "5") (pinfunction "5_5") (pintype "passive"))
      (node (ref "E1") (pin "56") (pinfunction "IO45_56") (pintype "bidirectional"))
    )
    (net (code "49") (name "MB10") (class "Default")
      (node (ref "BMB2P") (pin "3") (pinfunction "3_3") (pintype "passive"))
      (node (ref "E1") (pin "58") (pinfunction "IO47_58") (pintype "bidirectional"))
    )
    (net (code "50") (name "MB11") (class "Default")
      (node (ref "BMB2P") (pin "1") (pinfunction "1_1") (pintype "passive"))
      (node (ref "E1") (pin "60") (pinfunction "IO48_60") (pintype "bidirectional"))
    )
    (net (code "51") (name "Net-(E2A-C)") (class "Default")
      (node (ref "E2") (pin "2") (pinfunction "C_2") (pintype "passive"))
      (node (ref "R15") (pin "2") (pinfunction "2_2") (pintype "passive"))
    )
    (net (code "52") (name "Net-(E2A-EMIT)") (class "Default")
      (node (ref "E2") (pin "16") (pinfunction "EMIT_16") (pintype "passive"))
      (node (ref "R21") (pin "2") (pinfunction "2_2") (pintype "passive"))
      (node (ref "R23") (pin "2") (pinfunction "2_2") (pintype "passive"))
    )
    (net (code "53") (name "Net-(E2C-A)") (class "Default")
      (node (ref "E2") (pin "5") (pinfunction "A_5") (pintype "passive"))
      (node (ref "R11") (pin "1") (pinfunction "1_1") (pintype "passive"))
    )
    (net (code "54") (name "Net-(E3A-C1+)") (class "Default")
      (node (ref "C14") (pin "1") (pinfunction "1_1") (pintype "passive"))
      (node (ref "E3") (pin "1") (pinfunction "C1+_1") (pintype "bidirectional"))
    )
    (net (code "55") (name "Net-(E3A-C1-)") (class "Default")
      (node (ref "C14") (pin "2") (pinfunction "2_2") (pintype "passive"))
      (node (ref "E3") (pin "3") (pinfunction "C1-_3") (pintype "bidirectional"))
    )
    (net (code "56") (name "Net-(E3A-C2+)") (class "Default")
      (node (ref "C15") (pin "1") (pinfunction "1_1") (pintype "passive"))
      (node (ref "E3") (pin "4") (pinfunction "C2+_4") (pintype "bidirectional"))
    )
    (net (code "57") (name "Net-(E3A-C2-)") (class "Default")
      (node (ref "C15") (pin "2") (pinfunction "2_2") (pintype "passive"))
      (node (ref "E3") (pin "5") (pinfunction "C2-_5") (pintype "bidirectional"))
    )
    (net (code "58") (name "Net-(E3A-V+)") (class "Default")
      (node (ref "C16") (pin "1") (pinfunction "1_1") (pintype "passive"))
      (node (ref "E3") (pin "2") (pinfunction "V+_2") (pintype "bidirectional"))
    )
    (net (code "59") (name "Net-(E3A-V-)") (class "Default")
      (node (ref "C17") (pin "2") (pinfunction "2_2") (pintype "passive"))
      (node (ref "E3") (pin "6") (pinfunction "V-_6") (pintype "bidirectional"))
    )
    (net (code "60") (name "Net-(J2-CC1)") (class "Default")
      (node (ref "J2") (pin "A5") (pinfunction "CC1_A5") (pintype "bidirectional"))
      (node (ref "R3") (pin "1") (pinfunction "1_1") (pintype "passive"))
    )
    (net (code "61") (name "Net-(J2-CC2)") (class "Default")
      (node (ref "J2") (pin "B5") (pinfunction "CC2_B5") (pintype "bidirectional"))
      (node (ref "R4") (pin "1") (pinfunction "1_1") (pintype "passive"))
    )
    (net (code "62") (name "Net-(Q2-PadB)") (class "Default")
      (node (ref "Q2") (pin "B") (pinfunction "B_B") (pintype "passive"))
      (node (ref "R16") (pin "2") (pinfunction "2_2") (pintype "passive"))
    )
    (net (code "63") (name "READER_RUN+") (class "Default")
      (node (ref "J1") (pin "PP") (pinfunction "35_PP") (pintype "bidirectional"))
      (node (ref "R1") (pin "2") (pinfunction "2_2") (pintype "passive"))
      (node (ref "R21") (pin "1") (pinfunction "1_1") (pintype "passive"))
      (node (ref "R23") (pin "1") (pinfunction "1_1") (pintype "passive"))
    )
    (net (code "64") (name "RTS") (class "Default")
      (node (ref "E3") (pin "14") (pinfunction "T1OUT_14") (pintype "output"))
      (node (ref "J1") (pin "V") (pinfunction "18_V") (pintype "bidirectional"))
    )
    (net (code "65") (name "RXD232") (class "Default")
      (node (ref "E3") (pin "8") (pinfunction "R2IN_8") (pintype "input"))
      (node (ref "J1") (pin "J") (pinfunction "8_J") (pintype "bidirectional"))
    )
    (net (code "66") (name "RXDTTL") (class "Default")
      (node (ref "E3") (pin "9") (pinfunction "R2OUT_9") (pintype "output"))
      (node (ref "R16") (pin "1") (pinfunction "1_1") (pintype "passive"))
    )
    (net (code "67") (name "RX_20MA+") (class "Default")
      (node (ref "D1") (pin "C") (pinfunction "C_C") (pintype "passive"))
      (node (ref "J1") (pin "K") (pinfunction "9_K") (pintype "bidirectional"))
      (node (ref "R12") (pin "1") (pinfunction "1_1") (pintype "passive"))
    )
    (net (code "68") (name "RX_20MA-") (class "Default")
      (node (ref "D1") (pin "A") (pinfunction "A_A") (pintype "passive"))
      (node (ref "E2") (pin "8") (pinfunction "A_8") (pintype "passive"))
      (node (ref "J1") (pin "S") (pinfunction "15_S") (pintype "bidirectional"))
    )
    (net (code "69") (name "RX_DATA") (class "Default")
      (node (ref "E1") (pin "42") (pinfunction "IO33_42") (pintype "bidirectional"))
      (node (ref "J1") (pin "E") (pinfunction "5_E") (pintype "bidirectional"))
    )
    (net (code "70") (name "R_RUN") (class "Default")
      (node (ref "E1") (pin "40") (pinfunction "IO31_40") (pintype "bidirectional"))
      (node (ref "E2") (pin "1") (pinfunction "A_1") (pintype "passive"))
      (node (ref "E3") (pin "11") (pinfunction "T1IN_11") (pintype "input"))
    )
    (net (code "71") (name "TCK") (class "Default")
      (node (ref "E1") (pin "62") (pinfunction "TCK_62") (pintype "bidirectional"))
      (node (ref "PROG1") (pin "1") (pinfunction "1_1") (pintype "passive"))
    )
    (net (code "72") (name "TDI") (class "Default")
      (node (ref "E1") (pin "4") (pinfunction "TDI_4") (pintype "bidirectional"))
      (node (ref "PROG1") (pin "9") (pinfunction "9_9") (pintype "passive"))
    )
    (net (code "73") (name "TDO") (class "Default")
      (node (ref "E1") (pin "73") (pinfunction "TDO_73") (pintype "bidirectional"))
      (node (ref "PROG1") (pin "3") (pinfunction "3_3") (pintype "passive"))
    )
    (net (code "74") (name "TMS") (class "Default")
      (node (ref "E1") (pin "15") (pinfunction "TMS_15") (pintype "bidirectional"))
      (node (ref "PROG1") (pin "5") (pinfunction "5_5") (pintype "passive"))
    )
    (net (code "75") (name "TS1") (class "Default")
      (node (ref "BAC2P") (pin "3") (pinfunction "3_3") (pintype "passive"))
      (node (ref "E1") (pin "37") (pinfunction "IO30_37") (pintype "bidirectional"))
      (node (ref "R9") (pin "1") (pinfunction "1_1") (pintype "passive"))
    )
    (net (code "76") (name "TS3") (class "Default")
      (node (ref "BAC2P") (pin "5") (pinfunction "5_5") (pintype "passive"))
      (node (ref "E1") (pin "36") (pinfunction "IO29_36") (pintype "bidirectional"))
      (node (ref "R8") (pin "1") (pinfunction "1_1") (pintype "passive"))
    )
    (net (code "77") (name "TXD232") (class "Default")
      (node (ref "E3") (pin "7") (pinfunction "T2OUT_7") (pintype "output"))
      (node (ref "J1") (pin "F") (pinfunction "6_F") (pintype "bidirectional"))
    )
    (net (code "78") (name "TXDTTL") (class "Default")
      (node (ref "E1") (pin "41") (pinfunction "IO/PD2_41") (pintype "bidirectional"))
      (node (ref "E3") (pin "10") (pinfunction "T2IN_10") (pintype "input"))
      (node (ref "R11") (pin "2") (pinfunction "2_2") (pintype "passive"))
    )
    (net (code "79") (name "TX_20MA+") (class "Default")
      (node (ref "J1") (pin "AA") (pinfunction "23_AA") (pintype "bidirectional"))
      (node (ref "R13") (pin "2") (pinfunction "2_2") (pintype "passive"))
    )
    (net (code "80") (name "TX_20MA-") (class "Default")
      (node (ref "E2") (pin "11") (pinfunction "COL_11") (pintype "passive"))
      (node (ref "J1") (pin "KK") (pinfunction "31_KK") (pintype "bidirectional"))
    )
    (net (code "81") (name "VCC") (class "Default")
      (node (ref "C1") (pin "1") (pinfunction "1_1") (pintype "passive"))
      (node (ref "C10") (pin "1") (pinfunction "1_1") (pintype "passive"))
      (node (ref "C16") (pin "2") (pinfunction "2_2") (pintype "passive"))
      (node (ref "C2") (pin "1") (pinfunction "1_1") (pintype "passive"))
      (node (ref "C3") (pin "1") (pinfunction "1_1") (pintype "passive"))
      (node (ref "C4") (pin "1") (pinfunction "1_1") (pintype "passive"))
      (node (ref "C5") (pin "1") (pinfunction "1_1") (pintype "passive"))
      (node (ref "C6") (pin "1") (pinfunction "1_1") (pintype "passive"))
      (node (ref "C7") (pin "1") (pinfunction "1_1") (pintype "passive"))
      (node (ref "C8") (pin "1") (pinfunction "1_1") (pintype "passive"))
      (node (ref "C9") (pin "1") (pinfunction "1_1") (pintype "passive"))
      (node (ref "DS0") (pin "3") (pinfunction "3_3") (pintype "passive"))
      (node (ref "DS1") (pin "3") (pinfunction "3_3") (pintype "passive"))
      (node (ref "DS2") (pin "3") (pinfunction "3_3") (pintype "passive"))
      (node (ref "E1") (pin "18") (pinfunction "VCCIO_18") (pintype "power_in"))
      (node (ref "E1") (pin "3") (pinfunction "VCCIO_3") (pintype "power_in"))
      (node (ref "E1") (pin "34") (pinfunction "VCCIO_34") (pintype "power_in"))
      (node (ref "E1") (pin "39") (pinfunction "VCCINT_39") (pintype "power_in"))
      (node (ref "E1") (pin "51") (pinfunction "VCCIO_51") (pintype "power_in"))
      (node (ref "E1") (pin "66") (pinfunction "VCCIO_66") (pintype "power_in"))
      (node (ref "E1") (pin "82") (pinfunction "VCCIO_82") (pintype "power_in"))
      (node (ref "E1") (pin "91") (pinfunction "VCCINT_91") (pintype "power_in"))
      (node (ref "E2") (pin "15") (pinfunction "COL_15") (pintype "passive"))
      (node (ref "J2") (pin "A9") (pinfunction "VBUS_1_A9") (pintype "bidirectional"))
      (node (ref "J2") (pin "B9") (pinfunction "VBUS_2_B9") (pintype "bidirectional"))
      (node (ref "OSC") (pin "8") (pinfunction "VCC_8") (pintype "power_in"))
      (node (ref "OSC1") (pin "14") (pinfunction "VCC_14") (pintype "power_in"))
      (node (ref "PROG1") (pin "4") (pinfunction "4_4") (pintype "passive"))
      (node (ref "R12") (pin "2") (pinfunction "2_2") (pintype "passive"))
      (node (ref "R13") (pin "1") (pinfunction "1_1") (pintype "passive"))
      (node (ref "R14") (pin "2") (pinfunction "2_2") (pintype "passive"))
      (node (ref "R2") (pin "2") (pinfunction "2_2") (pintype "passive"))
    )
    (net (code "82") (name "X8_RATE") (class "Default")
      (node (ref "BAUD") (pin "10") (pinfunction "10_10") (pintype "passive"))
      (node (ref "BAUD") (pin "12") (pinfunction "12_12") (pintype "passive"))
      (node (ref "BAUD") (pin "14") (pinfunction "14_14") (pintype "passive"))
      (node (ref "BAUD") (pin "16") (pinfunction "16_16") (pintype "passive"))
      (node (ref "BAUD") (pin "18") (pinfunction "18_18") (pintype "passive"))
      (node (ref "BAUD") (pin "2") (pinfunction "2_2") (pintype "passive"))
      (node (ref "BAUD") (pin "20") (pinfunction "20_20") (pintype "passive"))
      (node (ref "BAUD") (pin "22") (pinfunction "22_22") (pintype "passive"))
      (node (ref "BAUD") (pin "24") (pinfunction "24_24") (pintype "passive"))
      (node (ref "BAUD") (pin "26") (pinfunction "26_26") (pintype "passive"))
      (node (ref "BAUD") (pin "4") (pinfunction "4_4") (pintype "passive"))
      (node (ref "BAUD") (pin "6") (pinfunction "6_6") (pintype "passive"))
      (node (ref "BAUD") (pin "8") (pinfunction "8_8") (pintype "passive"))
      (node (ref "E1") (pin "21") (pinfunction "IO16_21") (pintype "bidirectional"))
    )
    (net (code "83") (name "unconnected-(ACB1P-Pad19)") (class "Default")
      (node (ref "ACB1P") (pin "19") (pinfunction "19_19") (pintype "passive"))
    )
    (net (code "84") (name "unconnected-(ACB2P-Pad19)") (class "Default")
      (node (ref "ACB2P") (pin "19") (pinfunction "19_19") (pintype "passive"))
    )
    (net (code "85") (name "unconnected-(BAC1P-Pad19)") (class "Default")
      (node (ref "BAC1P") (pin "19") (pinfunction "19_19") (pintype "passive"))
    )
    (net (code "86") (name "unconnected-(BAC2P-Pad19)") (class "Default")
      (node (ref "BAC2P") (pin "19") (pinfunction "19_19") (pintype "passive"))
    )
    (net (code "87") (name "unconnected-(BMB1P-Pad19)") (class "Default")
      (node (ref "BMB1P") (pin "19") (pinfunction "19_19") (pintype "passive"))
    )
    (net (code "88") (name "unconnected-(BMB2P-Pad19)") (class "Default")
      (node (ref "BMB2P") (pin "19") (pinfunction "19_19") (pintype "passive"))
    )
    (net (code "89") (name "unconnected-(DAD1P-Pad19)") (class "Default")
      (node (ref "DAD1P") (pin "19") (pinfunction "19_19") (pintype "passive"))
    )
    (net (code "90") (name "unconnected-(DAD2P-Pad19)") (class "Default")
      (node (ref "DAD2P") (pin "19") (pinfunction "19_19") (pintype "passive"))
    )
    (net (code "91") (name "unconnected-(DAT1P-Pad19)") (class "Default")
      (node (ref "DAT1P") (pin "19") (pinfunction "19_19") (pintype "passive"))
    )
    (net (code "92") (name "unconnected-(DAT2P-Pad19)") (class "Default")
      (node (ref "DAT2P") (pin "19") (pinfunction "19_19") (pintype "passive"))
    )
    (net (code "93") (name "unconnected-(E1Q-IN{slash}OE1-Pad88)") (class "Default")
      (node (ref "E1") (pin "88") (pinfunction "IN/OE1_88") (pintype "input"))
    )
    (net (code "94") (name "unconnected-(E1Q-IO34-Pad44)") (class "Default")
      (node (ref "E1") (pin "44") (pinfunction "IO34_44") (pintype "bidirectional"))
    )
    (net (code "95") (name "unconnected-(E1Q-IO35-Pad45)") (class "Default")
      (node (ref "E1") (pin "45") (pinfunction "IO35_45") (pintype "bidirectional"))
    )
    (net (code "96") (name "unconnected-(E1Q-IO42-Pad53)") (class "Default")
      (node (ref "E1") (pin "53") (pinfunction "IO42_53") (pintype "bidirectional"))
    )
    (net (code "97") (name "unconnected-(E1Q-IO69-Pad92)") (class "Default")
      (node (ref "E1") (pin "92") (pinfunction "IO69_92") (pintype "bidirectional"))
    )
    (net (code "98") (name "unconnected-(E1Q-IO70-Pad93)") (class "Default")
      (node (ref "E1") (pin "93") (pinfunction "IO70_93") (pintype "bidirectional"))
    )
    (net (code "99") (name "unconnected-(E1Q-IO71-Pad94)") (class "Default")
      (node (ref "E1") (pin "94") (pinfunction "IO71_94") (pintype "bidirectional"))
    )
    (net (code "100") (name "unconnected-(E1Q-IO72-Pad96)") (class "Default")
      (node (ref "E1") (pin "96") (pinfunction "IO72_96") (pintype "bidirectional"))
    )
    (net (code "101") (name "unconnected-(E1Q-IO73-Pad97)") (class "Default")
      (node (ref "E1") (pin "97") (pinfunction "IO73_97") (pintype "bidirectional"))
    )
    (net (code "102") (name "unconnected-(E1Q-IO74-Pad98)") (class "Default")
      (node (ref "E1") (pin "98") (pinfunction "IO74_98") (pintype "bidirectional"))
    )
    (net (code "103") (name "unconnected-(E1Q-IO75-Pad99)") (class "Default")
      (node (ref "E1") (pin "99") (pinfunction "IO75_99") (pintype "bidirectional"))
    )
    (net (code "104") (name "unconnected-(E2B-A-Pad4)") (class "Default")
      (node (ref "E2") (pin "4") (pinfunction "A_4") (pintype "passive"))
    )
    (net (code "105") (name "unconnected-(E2B-C-Pad3)") (class "Default")
      (node (ref "E2") (pin "3") (pinfunction "C_3") (pintype "passive"))
    )
    (net (code "106") (name "unconnected-(E2B-COL-Pad14)") (class "Default")
      (node (ref "E2") (pin "14") (pinfunction "COL_14") (pintype "passive"))
    )
    (net (code "107") (name "unconnected-(E3A-R1OUT-Pad12)") (class "Default")
      (node (ref "E3") (pin "12") (pinfunction "R1OUT_12") (pintype "output"))
    )
    (net (code "108") (name "unconnected-(J1-4-PadD)") (class "Default")
      (node (ref "J1") (pin "D") (pinfunction "4_D") (pintype "bidirectional"))
    )
    (net (code "109") (name "unconnected-(J1-10-PadL)") (class "Default")
      (node (ref "J1") (pin "L") (pinfunction "10_L") (pintype "bidirectional"))
    )
    (net (code "110") (name "unconnected-(J1-12-PadN)") (class "Default")
      (node (ref "J1") (pin "N") (pinfunction "12_N") (pintype "bidirectional"))
    )
    (net (code "111") (name "unconnected-(J1-13-PadP)") (class "Default")
      (node (ref "J1") (pin "P") (pinfunction "13_P") (pintype "bidirectional"))
    )
    (net (code "112") (name "unconnected-(J1-14-PadR)") (class "Default")
      (node (ref "J1") (pin "R") (pinfunction "14_R") (pintype "bidirectional"))
    )
    (net (code "113") (name "unconnected-(J1-16-PadT)") (class "Default")
      (node (ref "J1") (pin "T") (pinfunction "16_T") (pintype "bidirectional"))
    )
    (net (code "114") (name "unconnected-(J1-17-PadU)") (class "Default")
      (node (ref "J1") (pin "U") (pinfunction "17_U") (pintype "bidirectional"))
    )
    (net (code "115") (name "unconnected-(J1-19-PadW)") (class "Default")
      (node (ref "J1") (pin "W") (pinfunction "19_W") (pintype "bidirectional"))
    )
    (net (code "116") (name "unconnected-(J1-20-PadX)") (class "Default")
      (node (ref "J1") (pin "X") (pinfunction "20_X") (pintype "bidirectional"))
    )
    (net (code "117") (name "unconnected-(J1-21-PadY)") (class "Default")
      (node (ref "J1") (pin "Y") (pinfunction "21_Y") (pintype "bidirectional"))
    )
    (net (code "118") (name "unconnected-(J1-22-PadZ)") (class "Default")
      (node (ref "J1") (pin "Z") (pinfunction "22_Z") (pintype "bidirectional"))
    )
    (net (code "119") (name "unconnected-(J1-24-PadBB)") (class "Default")
      (node (ref "J1") (pin "BB") (pinfunction "24_BB") (pintype "bidirectional"))
    )
    (net (code "120") (name "unconnected-(J1-25-PadCC)") (class "Default")
      (node (ref "J1") (pin "CC") (pinfunction "25_CC") (pintype "bidirectional"))
    )
    (net (code "121") (name "unconnected-(J1-28-PadFF)") (class "Default")
      (node (ref "J1") (pin "FF") (pinfunction "28_FF") (pintype "bidirectional"))
    )
    (net (code "122") (name "unconnected-(J1-29-PadHH)") (class "Default")
      (node (ref "J1") (pin "HH") (pinfunction "29_HH") (pintype "bidirectional"))
    )
    (net (code "123") (name "unconnected-(J1-30-PadJJ)") (class "Default")
      (node (ref "J1") (pin "JJ") (pinfunction "30_JJ") (pintype "bidirectional"))
    )
    (net (code "124") (name "unconnected-(J1-32-PadLL)") (class "Default")
      (node (ref "J1") (pin "LL") (pinfunction "32_LL") (pintype "bidirectional"))
    )
    (net (code "125") (name "unconnected-(J1-33-PadMM)") (class "Default")
      (node (ref "J1") (pin "MM") (pinfunction "33_MM") (pintype "bidirectional"))
    )
    (net (code "126") (name "unconnected-(J1-34-PadNN)") (class "Default")
      (node (ref "J1") (pin "NN") (pinfunction "34_NN") (pintype "bidirectional"))
    )
    (net (code "127") (name "unconnected-(J1-36-PadRR)") (class "Default")
      (node (ref "J1") (pin "RR") (pinfunction "36_RR") (pintype "bidirectional"))
    )
    (net (code "128") (name "unconnected-(J1-37-PadSS)") (class "Default")
      (node (ref "J1") (pin "SS") (pinfunction "37_SS") (pintype "bidirectional"))
    )
    (net (code "129") (name "unconnected-(J1-38-PadTT)") (class "Default")
      (node (ref "J1") (pin "TT") (pinfunction "38_TT") (pintype "bidirectional"))
    )
    (net (code "130") (name "unconnected-(PROG1-Pad6)") (class "Default")
      (node (ref "PROG1") (pin "6") (pinfunction "6_6") (pintype "passive"))
    )
    (net (code "131") (name "unconnected-(PROG1-Pad7)") (class "Default")
      (node (ref "PROG1") (pin "7") (pinfunction "7_7") (pintype "passive"))
    )
    (net (code "132") (name "unconnected-(PROG1-Pad8)") (class "Default")
      (node (ref "PROG1") (pin "8") (pinfunction "8_8") (pintype "passive"))
    )
    (net (code "133") (name "~{ACLR}") (class "Default")
      (node (ref "ACB2P") (pin "7") (pinfunction "7_7") (pintype "passive"))
      (node (ref "E1") (pin "76") (pinfunction "IO60_76") (pintype "bidirectional"))
    )
    (net (code "134") (name "~{ADDA}") (class "Default")
      (node (ref "DAD2P") (pin "5") (pinfunction "5_5") (pintype "passive"))
    )
    (net (code "135") (name "~{BREAK}") (class "Default")
      (node (ref "DAD2P") (pin "7") (pinfunction "7_7") (pintype "passive"))
    )
    (net (code "136") (name "~{BRQ}") (class "Default")
      (node (ref "DAD2P") (pin "11") (pinfunction "11_11") (pintype "passive"))
    )
    (net (code "137") (name "~{CANCR}") (class "Default")
      (node (ref "DAT2P") (pin "9") (pinfunction "9_9") (pintype "passive"))
    )
    (net (code "138") (name "~{CYC3}") (class "Default")
      (node (ref "DAT2P") (pin "11") (pinfunction "11_11") (pintype "passive"))
    )
    (net (code "139") (name "~{D-IN}") (class "Default")
      (node (ref "DAD2P") (pin "9") (pinfunction "9_9") (pintype "passive"))
    )
    (net (code "140") (name "~{DAD00}") (class "Default")
      (node (ref "DAD1P") (pin "17") (pinfunction "17_17") (pintype "passive"))
    )
    (net (code "141") (name "~{DAD01}") (class "Default")
      (node (ref "DAD1P") (pin "15") (pinfunction "15_15") (pintype "passive"))
    )
    (net (code "142") (name "~{DAD02}") (class "Default")
      (node (ref "DAD1P") (pin "13") (pinfunction "13_13") (pintype "passive"))
    )
    (net (code "143") (name "~{DAD03}") (class "Default")
      (node (ref "DAD1P") (pin "11") (pinfunction "11_11") (pintype "passive"))
    )
    (net (code "144") (name "~{DAD04}") (class "Default")
      (node (ref "DAD1P") (pin "9") (pinfunction "9_9") (pintype "passive"))
    )
    (net (code "145") (name "~{DAD05}") (class "Default")
      (node (ref "DAD1P") (pin "7") (pinfunction "7_7") (pintype "passive"))
    )
    (net (code "146") (name "~{DAD06}") (class "Default")
      (node (ref "DAD1P") (pin "5") (pinfunction "5_5") (pintype "passive"))
    )
    (net (code "147") (name "~{DAD07}") (class "Default")
      (node (ref "DAD1P") (pin "3") (pinfunction "3_3") (pintype "passive"))
    )
    (net (code "148") (name "~{DAD08}") (class "Default")
      (node (ref "DAD1P") (pin "1") (pinfunction "1_1") (pintype "passive"))
    )
    (net (code "149") (name "~{DAD09}") (class "Default")
      (node (ref "DAD2P") (pin "17") (pinfunction "17_17") (pintype "passive"))
    )
    (net (code "150") (name "~{DAD10}") (class "Default")
      (node (ref "DAD2P") (pin "15") (pinfunction "15_15") (pintype "passive"))
    )
    (net (code "151") (name "~{DAD11}") (class "Default")
      (node (ref "DAD2P") (pin "13") (pinfunction "13_13") (pintype "passive"))
    )
    (net (code "152") (name "~{DAT00}") (class "Default")
      (node (ref "DAT1P") (pin "17") (pinfunction "17_17") (pintype "passive"))
    )
    (net (code "153") (name "~{DAT01}") (class "Default")
      (node (ref "DAT1P") (pin "15") (pinfunction "15_15") (pintype "passive"))
    )
    (net (code "154") (name "~{DAT02}") (class "Default")
      (node (ref "DAT1P") (pin "13") (pinfunction "13_13") (pintype "passive"))
    )
    (net (code "155") (name "~{DAT03}") (class "Default")
      (node (ref "DAT1P") (pin "11") (pinfunction "11_11") (pintype "passive"))
    )
    (net (code "156") (name "~{DAT04}") (class "Default")
      (node (ref "DAT1P") (pin "9") (pinfunction "9_9") (pintype "passive"))
    )
    (net (code "157") (name "~{DAT05}") (class "Default")
      (node (ref "DAT1P") (pin "7") (pinfunction "7_7") (pintype "passive"))
    )
    (net (code "158") (name "~{DAT06}") (class "Default")
      (node (ref "DAT1P") (pin "5") (pinfunction "5_5") (pintype "passive"))
    )
    (net (code "159") (name "~{DAT07}") (class "Default")
      (node (ref "DAT1P") (pin "3") (pinfunction "3_3") (pintype "passive"))
    )
    (net (code "160") (name "~{DAT08}") (class "Default")
      (node (ref "DAT1P") (pin "1") (pinfunction "1_1") (pintype "passive"))
    )
    (net (code "161") (name "~{DAT09}") (class "Default")
      (node (ref "DAT2P") (pin "17") (pinfunction "17_17") (pintype "passive"))
    )
    (net (code "162") (name "~{DAT10}") (class "Default")
      (node (ref "DAT2P") (pin "15") (pinfunction "15_15") (pintype "passive"))
    )
    (net (code "163") (name "~{DAT11}") (class "Default")
      (node (ref "DAT2P") (pin "13") (pinfunction "13_13") (pintype "passive"))
    )
    (net (code "164") (name "~{EXDA0}") (class "Default")
      (node (ref "DAT2P") (pin "1") (pinfunction "1_1") (pintype "passive"))
    )
    (net (code "165") (name "~{EXDA1}") (class "Default")
      (node (ref "DAT2P") (pin "3") (pinfunction "3_3") (pintype "passive"))
    )
    (net (code "166") (name "~{EXDA2}") (class "Default")
      (node (ref "DAT2P") (pin "5") (pinfunction "5_5") (pintype "passive"))
    )
    (net (code "167") (name "~{IB00}") (class "Default")
      (node (ref "ACB1P") (pin "17") (pinfunction "17_17") (pintype "passive"))
      (node (ref "E1") (pin "64") (pinfunction "IO51_64") (pintype "bidirectional"))
    )
    (net (code "168") (name "~{IB01}") (class "Default")
      (node (ref "ACB1P") (pin "15") (pinfunction "15_15") (pintype "passive"))
      (node (ref "E1") (pin "67") (pinfunction "IO53_67") (pintype "bidirectional"))
    )
    (net (code "169") (name "~{IB02}") (class "Default")
      (node (ref "ACB1P") (pin "13") (pinfunction "13_13") (pintype "passive"))
      (node (ref "E1") (pin "69") (pinfunction "IO55_69") (pintype "bidirectional"))
    )
    (net (code "170") (name "~{IB03}") (class "Default")
      (node (ref "ACB1P") (pin "11") (pinfunction "11_11") (pintype "passive"))
      (node (ref "E1") (pin "71") (pinfunction "IO57_71") (pintype "bidirectional"))
    )
    (net (code "171") (name "~{IB04}") (class "Default")
      (node (ref "ACB1P") (pin "9") (pinfunction "9_9") (pintype "passive"))
      (node (ref "E1") (pin "75") (pinfunction "IO59_75") (pintype "bidirectional"))
    )
    (net (code "172") (name "~{IB05}") (class "Default")
      (node (ref "ACB1P") (pin "7") (pinfunction "7_7") (pintype "passive"))
      (node (ref "E1") (pin "77") (pinfunction "IO61_77") (pintype "bidirectional"))
    )
    (net (code "173") (name "~{IB06}") (class "Default")
      (node (ref "ACB1P") (pin "5") (pinfunction "5_5") (pintype "passive"))
      (node (ref "E1") (pin "79") (pinfunction "IO63_79") (pintype "bidirectional"))
    )
    (net (code "174") (name "~{IB07}") (class "Default")
      (node (ref "ACB1P") (pin "3") (pinfunction "3_3") (pintype "passive"))
      (node (ref "E1") (pin "81") (pinfunction "IO65_81") (pintype "bidirectional"))
    )
    (net (code "175") (name "~{IB08}") (class "Default")
      (node (ref "ACB1P") (pin "1") (pinfunction "1_1") (pintype "passive"))
      (node (ref "E1") (pin "84") (pinfunction "IO67_84") (pintype "bidirectional"))
    )
    (net (code "176") (name "~{IB09}") (class "Default")
      (node (ref "ACB2P") (pin "17") (pinfunction "17_17") (pintype "passive"))
      (node (ref "E1") (pin "63") (pinfunction "IO50_63") (pintype "bidirectional"))
    )
    (net (code "177") (name "~{IB10}") (class "Default")
      (node (ref "ACB2P") (pin "15") (pinfunction "15_15") (pintype "passive"))
      (node (ref "E1") (pin "65") (pinfunction "IO52_65") (pintype "bidirectional"))
    )
    (net (code "178") (name "~{IB11}") (class "Default")
      (node (ref "ACB2P") (pin "13") (pinfunction "13_13") (pintype "passive"))
      (node (ref "E1") (pin "68") (pinfunction "IO54_68") (pintype "bidirectional"))
    )
    (net (code "179") (name "~{IRQ}") (class "Default")
      (node (ref "ACB2P") (pin "9") (pinfunction "9_9") (pintype "passive"))
      (node (ref "E1") (pin "72") (pinfunction "IO58_72") (pintype "bidirectional"))
    )
    (net (code "180") (name "~{LINE}") (class "Default")
      (node (ref "ACB2P") (pin "1") (pinfunction "1_1") (pintype "passive"))
      (node (ref "E1") (pin "83") (pinfunction "IO66_83") (pintype "bidirectional"))
    )
    (net (code "181") (name "~{MB03}") (class "Default")
      (node (ref "BMB1P") (pin "11") (pinfunction "11_11") (pintype "passive"))
    )
    (net (code "182") (name "~{MB04}") (class "Default")
      (node (ref "BMB1P") (pin "7") (pinfunction "7_7") (pintype "passive"))
    )
    (net (code "183") (name "~{MB05}") (class "Default")
      (node (ref "BMB1P") (pin "3") (pinfunction "3_3") (pintype "passive"))
    )
    (net (code "184") (name "~{MB06}") (class "Default")
      (node (ref "BMB2P") (pin "17") (pinfunction "17_17") (pintype "passive"))
    )
    (net (code "185") (name "~{MB07}") (class "Default")
      (node (ref "BMB2P") (pin "13") (pinfunction "13_13") (pintype "passive"))
    )
    (net (code "186") (name "~{MB08}") (class "Default")
      (node (ref "BMB2P") (pin "9") (pinfunction "9_9") (pintype "passive"))
    )
    (net (code "187") (name "~{MNCR}") (class "Default")
      (node (ref "DAD2P") (pin "3") (pinfunction "3_3") (pintype "passive"))
    )
    (net (code "188") (name "~{RUN}") (class "Default")
      (node (ref "ACB2P") (pin "5") (pinfunction "5_5") (pintype "passive"))
      (node (ref "E1") (pin "78") (pinfunction "IO62_78") (pintype "bidirectional"))
    )
    (net (code "189") (name "~{SKIP}") (class "Default")
      (node (ref "ACB2P") (pin "11") (pinfunction "11_11") (pintype "passive"))
      (node (ref "E1") (pin "70") (pinfunction "IO56_70") (pintype "bidirectional"))
    )
    (net (code "190") (name "~{TTINST}") (class "Default")
      (node (ref "ACB2P") (pin "3") (pinfunction "3_3") (pintype "passive"))
      (node (ref "E1") (pin "80") (pinfunction "IO64_80") (pintype "bidirectional"))
    )
    (net (code "191") (name "~{WCOVF}") (class "Default")
      (node (ref "DAT2P") (pin "7") (pinfunction "7_7") (pintype "passive"))
    )
  )
)
